# MCU.net
KiCad netlist of a schematic drawn in Altium Designer
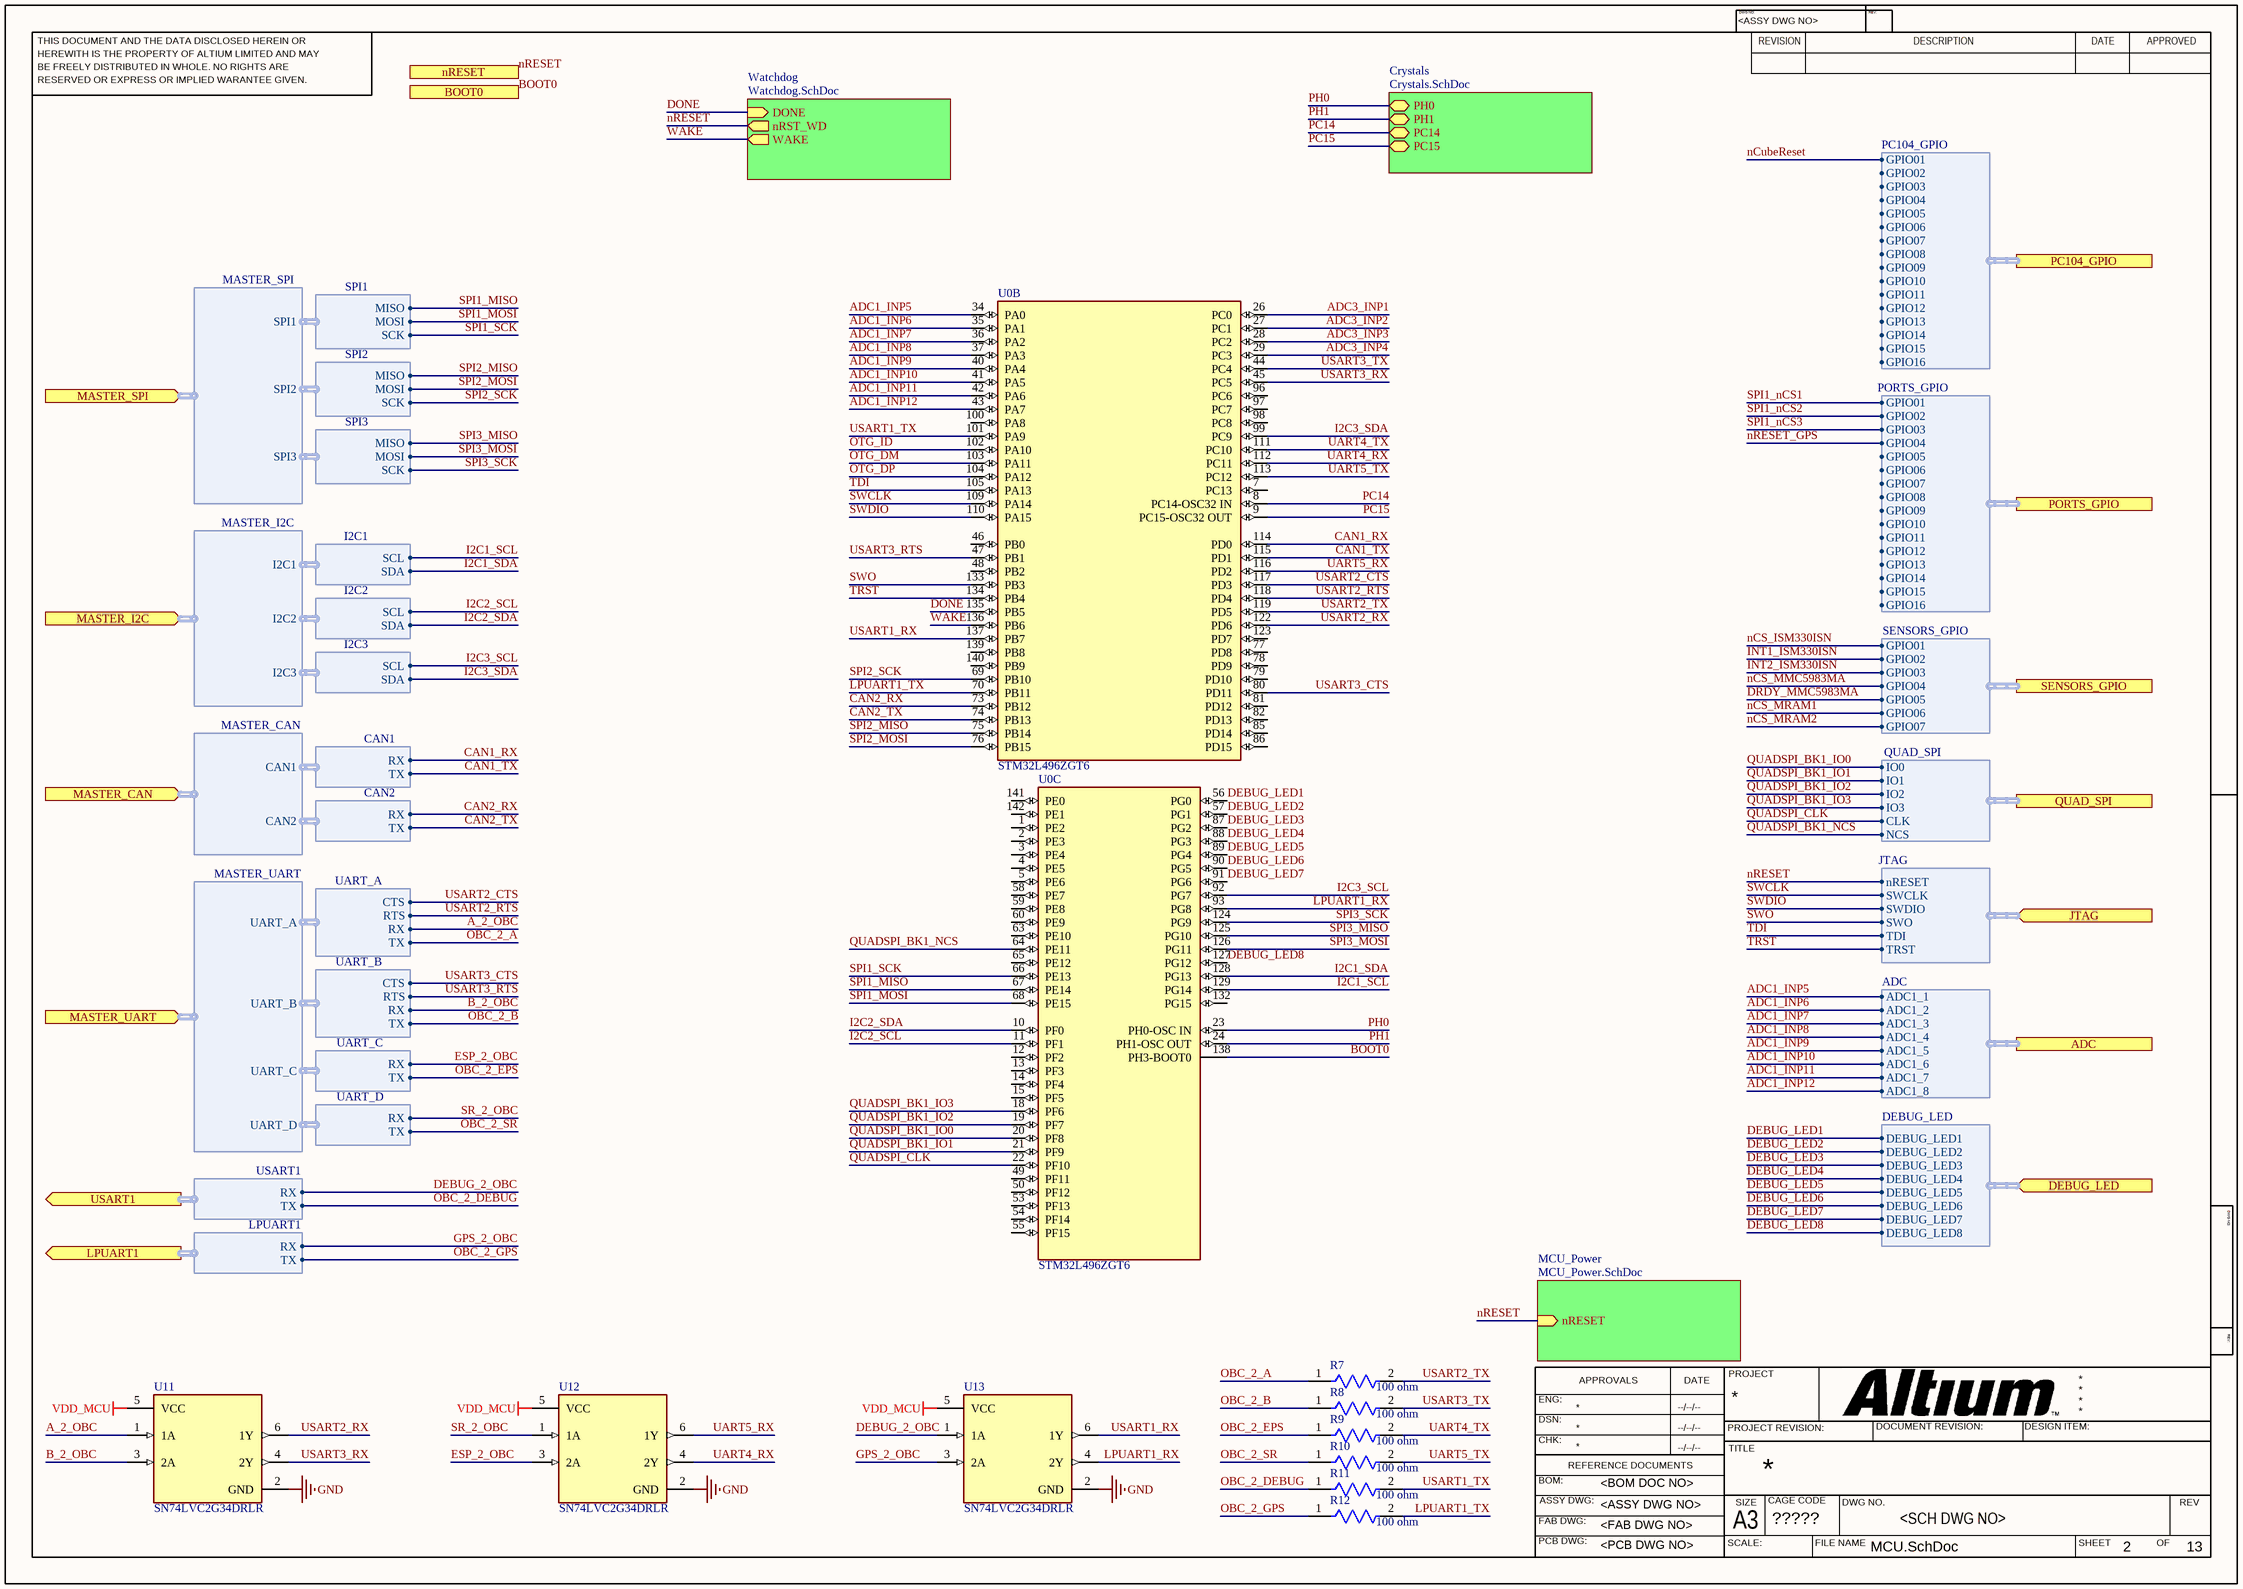
[diagram p0: MCU.SchDoc]

(export (version "E")
  (design (tool "Eeschema 10.0.6"))
  (components
    (comp (ref "R7")
      (value "100 ohm")
      (footprint "FP-ERJP03-MFG")
      (description "ERJ-P03F1000V SMD Chip Resistor, 100 Ohm, ± 1%, 200 mW, 0603 [1608 Metric], Thick Film, Anti-Surge")
      (fields (field (name "TOLERANCE") "1%"))
      (libsource (lib "Altium Content Vault") (part "1029c3af85768c4190bb7ad29bc67b5"))
    )
    (comp (ref "R8")
      (value "100 ohm")
      (footprint "FP-ERJP03-MFG")
      (description "ERJ-P03F1000V SMD Chip Resistor, 100 Ohm, ± 1%, 200 mW, 0603 [1608 Metric], Thick Film, Anti-Surge")
      (fields (field (name "TOLERANCE") "1%"))
      (libsource (lib "Altium Content Vault") (part "1029c3af85768c4190bb7ad29bc67b5"))
    )
    (comp (ref "R9")
      (value "100 ohm")
      (footprint "FP-ERJP03-MFG")
      (description "ERJ-P03F1000V SMD Chip Resistor, 100 Ohm, ± 1%, 200 mW, 0603 [1608 Metric], Thick Film, Anti-Surge")
      (fields (field (name "TOLERANCE") "1%"))
      (libsource (lib "Altium Content Vault") (part "1029c3af85768c4190bb7ad29bc67b5"))
    )
    (comp (ref "R10")
      (value "100 ohm")
      (footprint "FP-ERJP03-MFG")
      (description "ERJ-P03F1000V SMD Chip Resistor, 100 Ohm, ± 1%, 200 mW, 0603 [1608 Metric], Thick Film, Anti-Surge")
      (fields (field (name "TOLERANCE") "1%"))
      (libsource (lib "Altium Content Vault") (part "1029c3af85768c4190bb7ad29bc67b5"))
    )
    (comp (ref "R11")
      (value "100 ohm")
      (footprint "FP-ERJP03-MFG")
      (description "ERJ-P03F1000V SMD Chip Resistor, 100 Ohm, ± 1%, 200 mW, 0603 [1608 Metric], Thick Film, Anti-Surge")
      (fields (field (name "TOLERANCE") "1%"))
      (libsource (lib "Altium Content Vault") (part "1029c3af85768c4190bb7ad29bc67b5"))
    )
    (comp (ref "R12")
      (value "100 ohm")
      (footprint "FP-ERJP03-MFG")
      (description "ERJ-P03F1000V SMD Chip Resistor, 100 Ohm, ± 1%, 200 mW, 0603 [1608 Metric], Thick Film, Anti-Surge")
      (fields (field (name "TOLERANCE") "1%"))
      (libsource (lib "Altium Content Vault") (part "1029c3af85768c4190bb7ad29bc67b5"))
    )
    (comp (ref "U0")
      (value "STM32L496ZGT6")
      (footprint "FP-LQFP144-1A-MFG")
      (description "IC MCU 32BIT 1MB FLASH 144LQFP")
      (libsource (lib "Altium Content Vault") (part "f8f598a4e7bf6abd6ff1d35fb83b48f"))
    )
    (comp (ref "U11")
      (value "SN74LVC2G34DRLR")
      (footprint "FP-DRL0006A-MFG")
      (description "IC BUFFER NON-INVERT 5.5V 6SOT")
      (libsource (lib "Altium Content Vault") (part "59303bce76f5fafbc101ba271662c75"))
    )
    (comp (ref "U12")
      (value "SN74LVC2G34DRLR")
      (footprint "FP-DRL0006A-MFG")
      (description "IC BUFFER NON-INVERT 5.5V 6SOT")
      (libsource (lib "Altium Content Vault") (part "59303bce76f5fafbc101ba271662c75"))
    )
    (comp (ref "U13")
      (value "SN74LVC2G34DRLR")
      (footprint "FP-DRL0006A-MFG")
      (description "IC BUFFER NON-INVERT 5.5V 6SOT")
      (libsource (lib "Altium Content Vault") (part "59303bce76f5fafbc101ba271662c75"))
    )
  )
  (nets
    (net (code "26") (name "/ADC1_INP5") (class "Default")
      (node (ref "U0") (pin "34") (pinfunction "PA0_34") (pintype "bidirectional"))
    )
    (net (code "27") (name "/ADC1_INP6") (class "Default")
      (node (ref "U0") (pin "35") (pinfunction "PA1_35") (pintype "bidirectional"))
    )
    (net (code "28") (name "/ADC1_INP7") (class "Default")
      (node (ref "U0") (pin "36") (pinfunction "PA2_36") (pintype "bidirectional"))
    )
    (net (code "29") (name "/ADC1_INP8") (class "Default")
      (node (ref "U0") (pin "37") (pinfunction "PA3_37") (pintype "bidirectional"))
    )
    (net (code "30") (name "/ADC1_INP9") (class "Default")
      (node (ref "U0") (pin "40") (pinfunction "PA4_40") (pintype "bidirectional"))
    )
    (net (code "31") (name "/ADC1_INP10") (class "Default")
      (node (ref "U0") (pin "41") (pinfunction "PA5_41") (pintype "bidirectional"))
    )
    (net (code "32") (name "/ADC1_INP11") (class "Default")
      (node (ref "U0") (pin "42") (pinfunction "PA6_42") (pintype "bidirectional"))
    )
    (net (code "33") (name "/ADC1_INP12") (class "Default")
      (node (ref "U0") (pin "43") (pinfunction "PA7_43") (pintype "bidirectional"))
    )
    (net (code "34") (name "/ADC3_INP1") (class "Default")
      (node (ref "U0") (pin "26") (pinfunction "PC0_26") (pintype "bidirectional"))
    )
    (net (code "35") (name "/ADC3_INP2") (class "Default")
      (node (ref "U0") (pin "27") (pinfunction "PC1_27") (pintype "bidirectional"))
    )
    (net (code "36") (name "/ADC3_INP3") (class "Default")
      (node (ref "U0") (pin "28") (pinfunction "PC2_28") (pintype "bidirectional"))
    )
    (net (code "37") (name "/ADC3_INP4") (class "Default")
      (node (ref "U0") (pin "29") (pinfunction "PC3_29") (pintype "bidirectional"))
    )
    (net (code "38") (name "/A_2_OBC") (class "Default")
      (node (ref "U11") (pin "1") (pinfunction "1A_1") (pintype "input"))
    )
    (net (code "39") (name "/BOOT0") (class "Default")
      (node (ref "U0") (pin "138") (pinfunction "PH3-BOOT0_138") (pintype "passive"))
    )
    (net (code "40") (name "/B_2_OBC") (class "Default")
      (node (ref "U11") (pin "3") (pinfunction "2A_3") (pintype "input"))
    )
    (net (code "41") (name "/CAN1_RX") (class "Default")
      (node (ref "U0") (pin "114") (pinfunction "PD0_114") (pintype "bidirectional"))
    )
    (net (code "42") (name "/CAN1_TX") (class "Default")
      (node (ref "U0") (pin "115") (pinfunction "PD1_115") (pintype "bidirectional"))
    )
    (net (code "43") (name "/CAN2_RX") (class "Default")
      (node (ref "U0") (pin "73") (pinfunction "PB12_73") (pintype "bidirectional"))
    )
    (net (code "44") (name "/CAN2_TX") (class "Default")
      (node (ref "U0") (pin "74") (pinfunction "PB13_74") (pintype "bidirectional"))
    )
    (net (code "45") (name "/DEBUG_2_OBC") (class "Default")
      (node (ref "U13") (pin "1") (pinfunction "1A_1") (pintype "input"))
    )
    (net (code "46") (name "/DEBUG_LED1") (class "Default")
      (node (ref "U0") (pin "56") (pinfunction "PG0_56") (pintype "bidirectional"))
    )
    (net (code "47") (name "/DEBUG_LED2") (class "Default")
      (node (ref "U0") (pin "57") (pinfunction "PG1_57") (pintype "bidirectional"))
    )
    (net (code "48") (name "/DEBUG_LED3") (class "Default")
      (node (ref "U0") (pin "87") (pinfunction "PG2_87") (pintype "bidirectional"))
    )
    (net (code "49") (name "/DEBUG_LED4") (class "Default")
      (node (ref "U0") (pin "88") (pinfunction "PG3_88") (pintype "bidirectional"))
    )
    (net (code "50") (name "/DEBUG_LED5") (class "Default")
      (node (ref "U0") (pin "89") (pinfunction "PG4_89") (pintype "bidirectional"))
    )
    (net (code "51") (name "/DEBUG_LED6") (class "Default")
      (node (ref "U0") (pin "90") (pinfunction "PG5_90") (pintype "bidirectional"))
    )
    (net (code "52") (name "/DEBUG_LED7") (class "Default")
      (node (ref "U0") (pin "91") (pinfunction "PG6_91") (pintype "bidirectional"))
    )
    (net (code "53") (name "/DEBUG_LED8") (class "Default")
      (node (ref "U0") (pin "127") (pinfunction "PG12_127") (pintype "bidirectional"))
    )
    (net (code "54") (name "/DONE") (class "Default")
      (node (ref "U0") (pin "135") (pinfunction "PB5_135") (pintype "bidirectional"))
    )
    (net (code "56") (name "/ESP_2_OBC") (class "Default")
      (node (ref "U12") (pin "3") (pinfunction "2A_3") (pintype "input"))
    )
    (net (code "57") (name "/GPS_2_OBC") (class "Default")
      (node (ref "U13") (pin "3") (pinfunction "2A_3") (pintype "input"))
    )
    (net (code "58") (name "/I2C1_SCL") (class "Default")
      (node (ref "U0") (pin "129") (pinfunction "PG14_129") (pintype "bidirectional"))
    )
    (net (code "59") (name "/I2C1_SDA") (class "Default")
      (node (ref "U0") (pin "128") (pinfunction "PG13_128") (pintype "bidirectional"))
    )
    (net (code "60") (name "/I2C2_SCL") (class "Default")
      (node (ref "U0") (pin "11") (pinfunction "PF1_11") (pintype "bidirectional"))
    )
    (net (code "61") (name "/I2C2_SDA") (class "Default")
      (node (ref "U0") (pin "10") (pinfunction "PF0_10") (pintype "bidirectional"))
    )
    (net (code "62") (name "/I2C3_SCL") (class "Default")
      (node (ref "U0") (pin "92") (pinfunction "PG7_92") (pintype "bidirectional"))
    )
    (net (code "63") (name "/I2C3_SDA") (class "Default")
      (node (ref "U0") (pin "99") (pinfunction "PC9_99") (pintype "bidirectional"))
    )
    (net (code "66") (name "/LPUART1_RX") (class "Default")
      (node (ref "U0") (pin "93") (pinfunction "PG8_93") (pintype "bidirectional"))
      (node (ref "U13") (pin "4") (pinfunction "2Y_4") (pintype "output"))
    )
    (net (code "67") (name "/LPUART1_TX") (class "Default")
      (node (ref "R12") (pin "2") (pinfunction "2_2") (pintype "passive"))
      (node (ref "U0") (pin "70") (pinfunction "PB11_70") (pintype "bidirectional"))
    )
    (net (code "71") (name "/OBC_2_A") (class "Default")
      (node (ref "R7") (pin "1") (pinfunction "1_1") (pintype "passive"))
    )
    (net (code "72") (name "/OBC_2_B") (class "Default")
      (node (ref "R8") (pin "1") (pinfunction "1_1") (pintype "passive"))
    )
    (net (code "73") (name "/OBC_2_DEBUG") (class "Default")
      (node (ref "R11") (pin "1") (pinfunction "1_1") (pintype "passive"))
    )
    (net (code "74") (name "/OBC_2_EPS") (class "Default")
      (node (ref "R9") (pin "1") (pinfunction "1_1") (pintype "passive"))
    )
    (net (code "75") (name "/OBC_2_GPS") (class "Default")
      (node (ref "R12") (pin "1") (pinfunction "1_1") (pintype "passive"))
    )
    (net (code "76") (name "/OBC_2_SR") (class "Default")
      (node (ref "R10") (pin "1") (pinfunction "1_1") (pintype "passive"))
    )
    (net (code "77") (name "/OTG_DM") (class "Default")
      (node (ref "U0") (pin "103") (pinfunction "PA11_103") (pintype "bidirectional"))
    )
    (net (code "78") (name "/OTG_DP") (class "Default")
      (node (ref "U0") (pin "104") (pinfunction "PA12_104") (pintype "bidirectional"))
    )
    (net (code "79") (name "/OTG_ID") (class "Default")
      (node (ref "U0") (pin "102") (pinfunction "PA10_102") (pintype "bidirectional"))
    )
    (net (code "80") (name "/PC14") (class "Default")
      (node (ref "U0") (pin "8") (pinfunction "PC14-OSC32_IN_8") (pintype "bidirectional"))
    )
    (net (code "81") (name "/PC15") (class "Default")
      (node (ref "U0") (pin "9") (pinfunction "PC15-OSC32_OUT_9") (pintype "bidirectional"))
    )
    (net (code "82") (name "/PH0") (class "Default")
      (node (ref "U0") (pin "23") (pinfunction "PH0-OSC_IN_23") (pintype "bidirectional"))
    )
    (net (code "83") (name "/PH1") (class "Default")
      (node (ref "U0") (pin "24") (pinfunction "PH1-OSC_OUT_24") (pintype "bidirectional"))
    )
    (net (code "84") (name "/QUADSPI_BK1_IO0") (class "Default")
      (node (ref "U0") (pin "20") (pinfunction "PF8_20") (pintype "bidirectional"))
    )
    (net (code "85") (name "/QUADSPI_BK1_IO1") (class "Default")
      (node (ref "U0") (pin "21") (pinfunction "PF9_21") (pintype "bidirectional"))
    )
    (net (code "86") (name "/QUADSPI_BK1_IO2") (class "Default")
      (node (ref "U0") (pin "19") (pinfunction "PF7_19") (pintype "bidirectional"))
    )
    (net (code "87") (name "/QUADSPI_BK1_IO3") (class "Default")
      (node (ref "U0") (pin "18") (pinfunction "PF6_18") (pintype "bidirectional"))
    )
    (net (code "88") (name "/QUADSPI_BK1_NCS") (class "Default")
      (node (ref "U0") (pin "64") (pinfunction "PE11_64") (pintype "bidirectional"))
    )
    (net (code "89") (name "/QUADSPI_CLK") (class "Default")
      (node (ref "U0") (pin "22") (pinfunction "PF10_22") (pintype "bidirectional"))
    )
    (net (code "90") (name "/SPI1_MISO") (class "Default")
      (node (ref "U0") (pin "67") (pinfunction "PE14_67") (pintype "bidirectional"))
    )
    (net (code "91") (name "/SPI1_MOSI") (class "Default")
      (node (ref "U0") (pin "68") (pinfunction "PE15_68") (pintype "bidirectional"))
    )
    (net (code "92") (name "/SPI1_SCK") (class "Default")
      (node (ref "U0") (pin "66") (pinfunction "PE13_66") (pintype "bidirectional"))
    )
    (net (code "96") (name "/SPI2_MISO") (class "Default")
      (node (ref "U0") (pin "75") (pinfunction "PB14_75") (pintype "bidirectional"))
    )
    (net (code "97") (name "/SPI2_MOSI") (class "Default")
      (node (ref "U0") (pin "76") (pinfunction "PB15_76") (pintype "bidirectional"))
    )
    (net (code "98") (name "/SPI2_SCK") (class "Default")
      (node (ref "U0") (pin "69") (pinfunction "PB10_69") (pintype "bidirectional"))
    )
    (net (code "99") (name "/SPI3_MISO") (class "Default")
      (node (ref "U0") (pin "125") (pinfunction "PG10_125") (pintype "bidirectional"))
    )
    (net (code "100") (name "/SPI3_MOSI") (class "Default")
      (node (ref "U0") (pin "126") (pinfunction "PG11_126") (pintype "bidirectional"))
    )
    (net (code "101") (name "/SPI3_SCK") (class "Default")
      (node (ref "U0") (pin "124") (pinfunction "PG9_124") (pintype "bidirectional"))
    )
    (net (code "102") (name "/SR_2_OBC") (class "Default")
      (node (ref "U12") (pin "1") (pinfunction "1A_1") (pintype "input"))
    )
    (net (code "103") (name "/SWCLK") (class "Default")
      (node (ref "U0") (pin "109") (pinfunction "PA14_109") (pintype "bidirectional"))
    )
    (net (code "104") (name "/SWDIO") (class "Default")
      (node (ref "U0") (pin "110") (pinfunction "PA15_110") (pintype "bidirectional"))
    )
    (net (code "105") (name "/SWO") (class "Default")
      (node (ref "U0") (pin "133") (pinfunction "PB3_133") (pintype "bidirectional"))
    )
    (net (code "106") (name "/TDI") (class "Default")
      (node (ref "U0") (pin "105") (pinfunction "PA13_105") (pintype "bidirectional"))
    )
    (net (code "107") (name "/TRST") (class "Default")
      (node (ref "U0") (pin "134") (pinfunction "PB4_134") (pintype "bidirectional"))
    )
    (net (code "108") (name "/UART4_RX") (class "Default")
      (node (ref "U0") (pin "112") (pinfunction "PC11_112") (pintype "bidirectional"))
      (node (ref "U12") (pin "4") (pinfunction "2Y_4") (pintype "output"))
    )
    (net (code "109") (name "/UART4_TX") (class "Default")
      (node (ref "R9") (pin "2") (pinfunction "2_2") (pintype "passive"))
      (node (ref "U0") (pin "111") (pinfunction "PC10_111") (pintype "bidirectional"))
    )
    (net (code "110") (name "/UART5_RX") (class "Default")
      (node (ref "U0") (pin "116") (pinfunction "PD2_116") (pintype "bidirectional"))
      (node (ref "U12") (pin "6") (pinfunction "1Y_6") (pintype "output"))
    )
    (net (code "111") (name "/UART5_TX") (class "Default")
      (node (ref "R10") (pin "2") (pinfunction "2_2") (pintype "passive"))
      (node (ref "U0") (pin "113") (pinfunction "PC12_113") (pintype "bidirectional"))
    )
    (net (code "112") (name "/USART1_RX") (class "Default")
      (node (ref "U0") (pin "137") (pinfunction "PB7_137") (pintype "bidirectional"))
      (node (ref "U13") (pin "6") (pinfunction "1Y_6") (pintype "output"))
    )
    (net (code "113") (name "/USART1_TX") (class "Default")
      (node (ref "R11") (pin "2") (pinfunction "2_2") (pintype "passive"))
      (node (ref "U0") (pin "101") (pinfunction "PA9_101") (pintype "bidirectional"))
    )
    (net (code "114") (name "/USART2_CTS") (class "Default")
      (node (ref "U0") (pin "117") (pinfunction "PD3_117") (pintype "bidirectional"))
    )
    (net (code "115") (name "/USART2_RTS") (class "Default")
      (node (ref "U0") (pin "118") (pinfunction "PD4_118") (pintype "bidirectional"))
    )
    (net (code "116") (name "/USART2_RX") (class "Default")
      (node (ref "U0") (pin "122") (pinfunction "PD6_122") (pintype "bidirectional"))
      (node (ref "U11") (pin "6") (pinfunction "1Y_6") (pintype "output"))
    )
    (net (code "117") (name "/USART2_TX") (class "Default")
      (node (ref "R7") (pin "2") (pinfunction "2_2") (pintype "passive"))
      (node (ref "U0") (pin "119") (pinfunction "PD5_119") (pintype "bidirectional"))
    )
    (net (code "118") (name "/USART3_CTS") (class "Default")
      (node (ref "U0") (pin "80") (pinfunction "PD11_80") (pintype "bidirectional"))
    )
    (net (code "119") (name "/USART3_RTS") (class "Default")
      (node (ref "U0") (pin "47") (pinfunction "PB1_47") (pintype "bidirectional"))
    )
    (net (code "120") (name "/USART3_RX") (class "Default")
      (node (ref "U0") (pin "45") (pinfunction "PC5_45") (pintype "bidirectional"))
      (node (ref "U11") (pin "4") (pinfunction "2Y_4") (pintype "output"))
    )
    (net (code "121") (name "/USART3_TX") (class "Default")
      (node (ref "R8") (pin "2") (pinfunction "2_2") (pintype "passive"))
      (node (ref "U0") (pin "44") (pinfunction "PC4_44") (pintype "bidirectional"))
    )
    (net (code "122") (name "/WAKE") (class "Default")
      (node (ref "U0") (pin "136") (pinfunction "PB6_136") (pintype "bidirectional"))
    )
    (net (code "152") (name "GND") (class "Default")
      (node (ref "U11") (pin "2") (pinfunction "GND_2") (pintype "power_in"))
      (node (ref "U12") (pin "2") (pinfunction "GND_2") (pintype "power_in"))
      (node (ref "U13") (pin "2") (pinfunction "GND_2") (pintype "power_in"))
    )
    (net (code "153") (name "VDD_MCU") (class "Default")
      (node (ref "U11") (pin "5") (pinfunction "VCC_5") (pintype "power_in"))
      (node (ref "U12") (pin "5") (pinfunction "VCC_5") (pintype "power_in"))
      (node (ref "U13") (pin "5") (pinfunction "VCC_5") (pintype "power_in"))
    )
    (net (code "154") (name "unconnected-(U0B-PA8-Pad100)") (class "Default")
      (node (ref "U0") (pin "100") (pinfunction "PA8_100") (pintype "bidirectional"))
    )
    (net (code "155") (name "unconnected-(U0B-PB0-Pad46)") (class "Default")
      (node (ref "U0") (pin "46") (pinfunction "PB0_46") (pintype "bidirectional"))
    )
    (net (code "156") (name "unconnected-(U0B-PB2-Pad48)") (class "Default")
      (node (ref "U0") (pin "48") (pinfunction "PB2_48") (pintype "bidirectional"))
    )
    (net (code "157") (name "unconnected-(U0B-PB8-Pad139)") (class "Default")
      (node (ref "U0") (pin "139") (pinfunction "PB8_139") (pintype "bidirectional"))
    )
    (net (code "158") (name "unconnected-(U0B-PB9-Pad140)") (class "Default")
      (node (ref "U0") (pin "140") (pinfunction "PB9_140") (pintype "bidirectional"))
    )
    (net (code "159") (name "unconnected-(U0B-PC6-Pad96)") (class "Default")
      (node (ref "U0") (pin "96") (pinfunction "PC6_96") (pintype "bidirectional"))
    )
    (net (code "160") (name "unconnected-(U0B-PC7-Pad97)") (class "Default")
      (node (ref "U0") (pin "97") (pinfunction "PC7_97") (pintype "bidirectional"))
    )
    (net (code "161") (name "unconnected-(U0B-PC8-Pad98)") (class "Default")
      (node (ref "U0") (pin "98") (pinfunction "PC8_98") (pintype "bidirectional"))
    )
    (net (code "162") (name "unconnected-(U0B-PC13-Pad7)") (class "Default")
      (node (ref "U0") (pin "7") (pinfunction "PC13_7") (pintype "bidirectional"))
    )
    (net (code "163") (name "unconnected-(U0B-PD7-Pad123)") (class "Default")
      (node (ref "U0") (pin "123") (pinfunction "PD7_123") (pintype "bidirectional"))
    )
    (net (code "164") (name "unconnected-(U0B-PD8-Pad77)") (class "Default")
      (node (ref "U0") (pin "77") (pinfunction "PD8_77") (pintype "bidirectional"))
    )
    (net (code "165") (name "unconnected-(U0B-PD9-Pad78)") (class "Default")
      (node (ref "U0") (pin "78") (pinfunction "PD9_78") (pintype "bidirectional"))
    )
    (net (code "166") (name "unconnected-(U0B-PD10-Pad79)") (class "Default")
      (node (ref "U0") (pin "79") (pinfunction "PD10_79") (pintype "bidirectional"))
    )
    (net (code "167") (name "unconnected-(U0B-PD12-Pad81)") (class "Default")
      (node (ref "U0") (pin "81") (pinfunction "PD12_81") (pintype "bidirectional"))
    )
    (net (code "168") (name "unconnected-(U0B-PD13-Pad82)") (class "Default")
      (node (ref "U0") (pin "82") (pinfunction "PD13_82") (pintype "bidirectional"))
    )
    (net (code "169") (name "unconnected-(U0B-PD14-Pad85)") (class "Default")
      (node (ref "U0") (pin "85") (pinfunction "PD14_85") (pintype "bidirectional"))
    )
    (net (code "170") (name "unconnected-(U0B-PD15-Pad86)") (class "Default")
      (node (ref "U0") (pin "86") (pinfunction "PD15_86") (pintype "bidirectional"))
    )
    (net (code "171") (name "unconnected-(U0C-PE0-Pad141)") (class "Default")
      (node (ref "U0") (pin "141") (pinfunction "PE0_141") (pintype "bidirectional"))
    )
    (net (code "172") (name "unconnected-(U0C-PE1-Pad142)") (class "Default")
      (node (ref "U0") (pin "142") (pinfunction "PE1_142") (pintype "bidirectional"))
    )
    (net (code "173") (name "unconnected-(U0C-PE2-Pad1)") (class "Default")
      (node (ref "U0") (pin "1") (pinfunction "PE2_1") (pintype "bidirectional"))
    )
    (net (code "174") (name "unconnected-(U0C-PE3-Pad2)") (class "Default")
      (node (ref "U0") (pin "2") (pinfunction "PE3_2") (pintype "bidirectional"))
    )
    (net (code "175") (name "unconnected-(U0C-PE4-Pad3)") (class "Default")
      (node (ref "U0") (pin "3") (pinfunction "PE4_3") (pintype "bidirectional"))
    )
    (net (code "176") (name "unconnected-(U0C-PE5-Pad4)") (class "Default")
      (node (ref "U0") (pin "4") (pinfunction "PE5_4") (pintype "bidirectional"))
    )
    (net (code "177") (name "unconnected-(U0C-PE6-Pad5)") (class "Default")
      (node (ref "U0") (pin "5") (pinfunction "PE6_5") (pintype "bidirectional"))
    )
    (net (code "178") (name "unconnected-(U0C-PE7-Pad58)") (class "Default")
      (node (ref "U0") (pin "58") (pinfunction "PE7_58") (pintype "bidirectional"))
    )
    (net (code "179") (name "unconnected-(U0C-PE8-Pad59)") (class "Default")
      (node (ref "U0") (pin "59") (pinfunction "PE8_59") (pintype "bidirectional"))
    )
    (net (code "180") (name "unconnected-(U0C-PE9-Pad60)") (class "Default")
      (node (ref "U0") (pin "60") (pinfunction "PE9_60") (pintype "bidirectional"))
    )
    (net (code "181") (name "unconnected-(U0C-PE10-Pad63)") (class "Default")
      (node (ref "U0") (pin "63") (pinfunction "PE10_63") (pintype "bidirectional"))
    )
    (net (code "182") (name "unconnected-(U0C-PE12-Pad65)") (class "Default")
      (node (ref "U0") (pin "65") (pinfunction "PE12_65") (pintype "bidirectional"))
    )
    (net (code "183") (name "unconnected-(U0C-PF2-Pad12)") (class "Default")
      (node (ref "U0") (pin "12") (pinfunction "PF2_12") (pintype "bidirectional"))
    )
    (net (code "184") (name "unconnected-(U0C-PF3-Pad13)") (class "Default")
      (node (ref "U0") (pin "13") (pinfunction "PF3_13") (pintype "bidirectional"))
    )
    (net (code "185") (name "unconnected-(U0C-PF4-Pad14)") (class "Default")
      (node (ref "U0") (pin "14") (pinfunction "PF4_14") (pintype "bidirectional"))
    )
    (net (code "186") (name "unconnected-(U0C-PF5-Pad15)") (class "Default")
      (node (ref "U0") (pin "15") (pinfunction "PF5_15") (pintype "bidirectional"))
    )
    (net (code "187") (name "unconnected-(U0C-PF11-Pad49)") (class "Default")
      (node (ref "U0") (pin "49") (pinfunction "PF11_49") (pintype "bidirectional"))
    )
    (net (code "188") (name "unconnected-(U0C-PF12-Pad50)") (class "Default")
      (node (ref "U0") (pin "50") (pinfunction "PF12_50") (pintype "bidirectional"))
    )
    (net (code "189") (name "unconnected-(U0C-PF13-Pad53)") (class "Default")
      (node (ref "U0") (pin "53") (pinfunction "PF13_53") (pintype "bidirectional"))
    )
    (net (code "190") (name "unconnected-(U0C-PF14-Pad54)") (class "Default")
      (node (ref "U0") (pin "54") (pinfunction "PF14_54") (pintype "bidirectional"))
    )
    (net (code "191") (name "unconnected-(U0C-PF15-Pad55)") (class "Default")
      (node (ref "U0") (pin "55") (pinfunction "PF15_55") (pintype "bidirectional"))
    )
    (net (code "192") (name "unconnected-(U0C-PG15-Pad132)") (class "Default")
      (node (ref "U0") (pin "132") (pinfunction "PG15_132") (pintype "bidirectional"))
    )
  )
)
